# avionicsboard.net
KiCad netlist of a schematic drawn in EAGLE
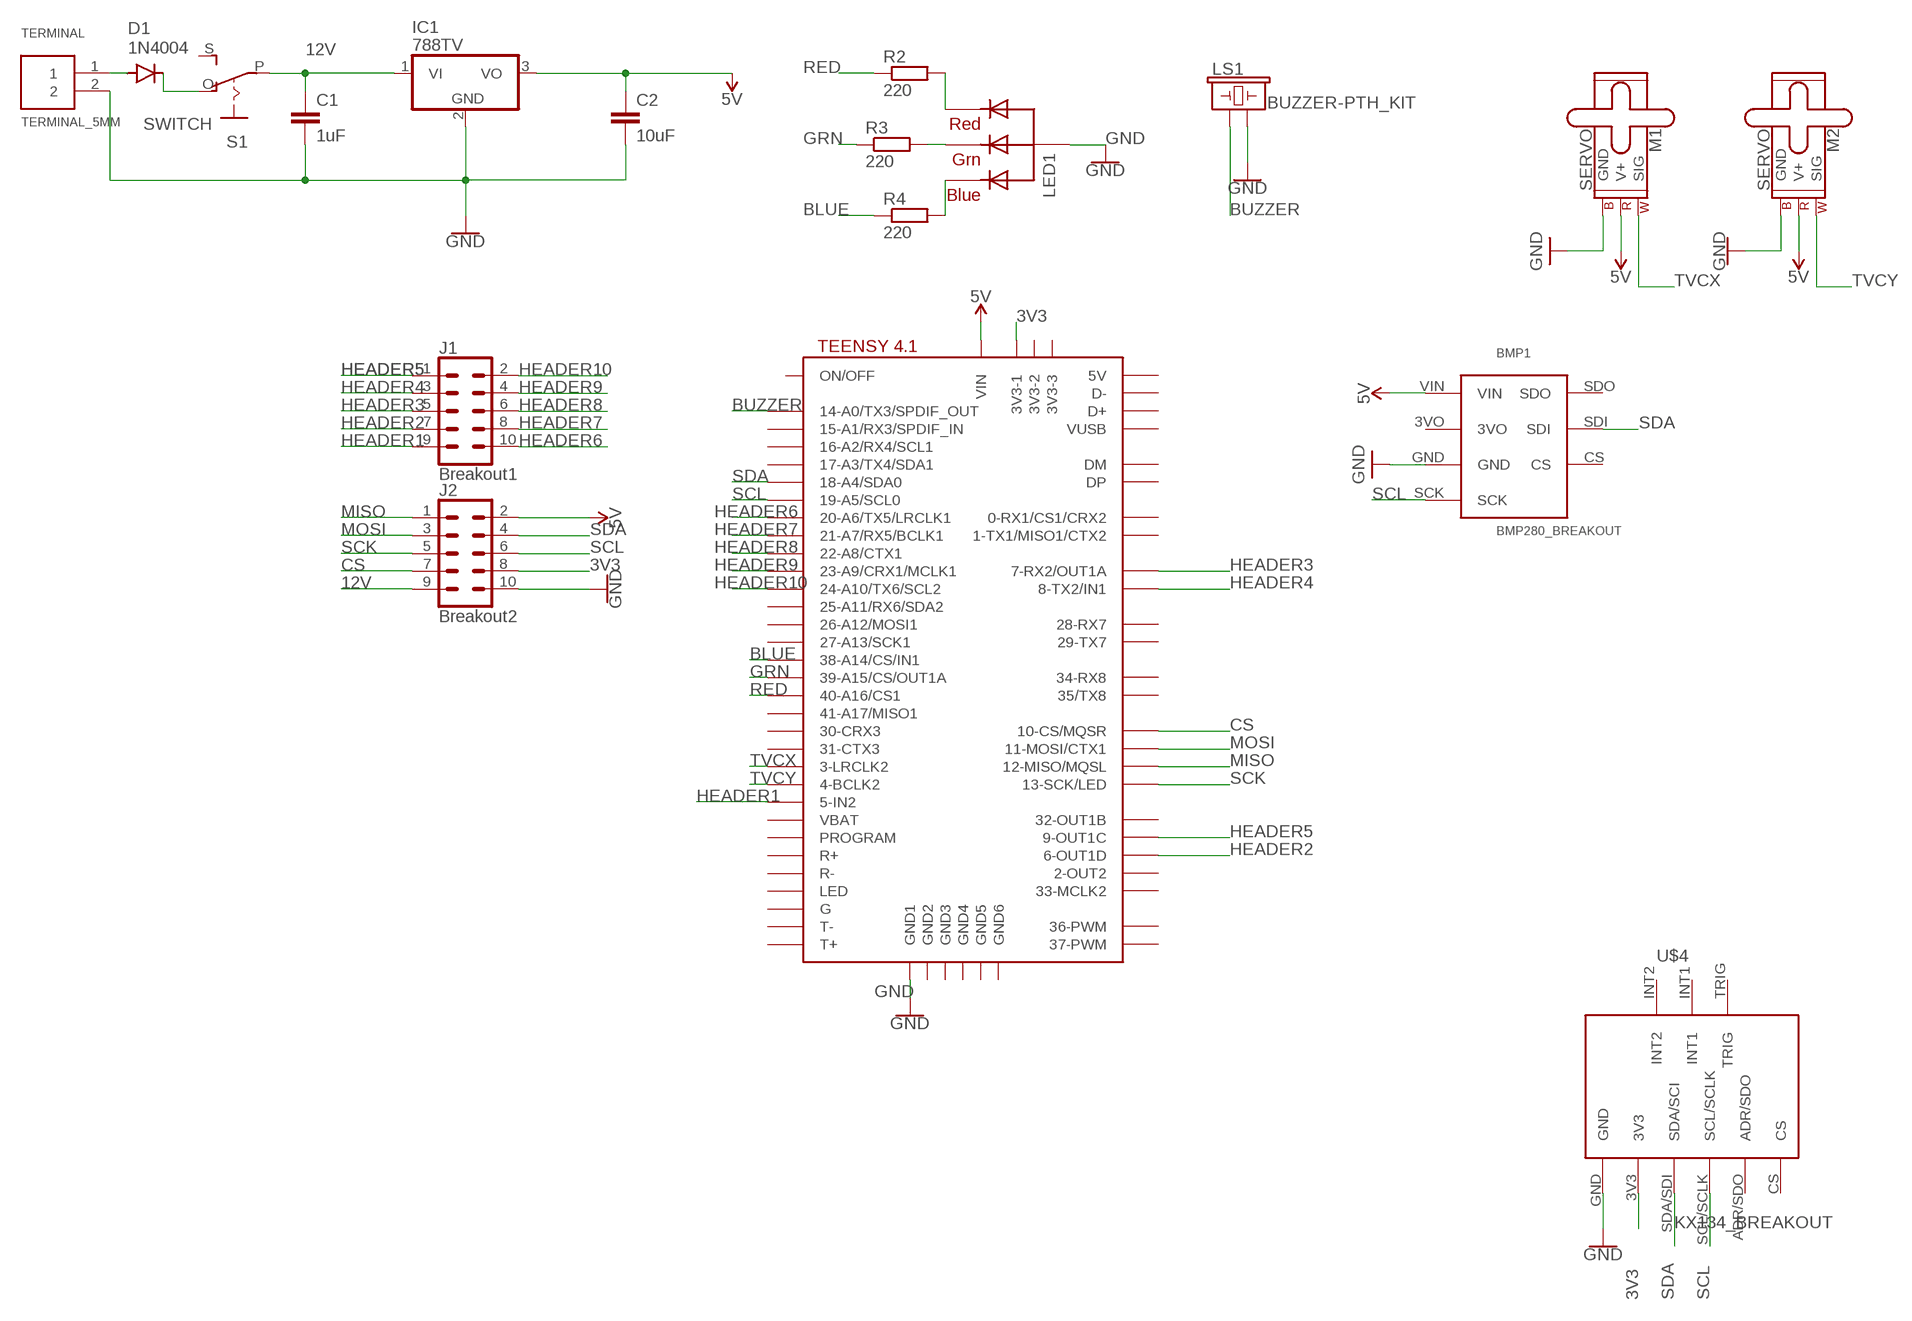
[diagram p0: schematic, sheet 1]

(export (version "E")
  (design (tool "Eeschema 10.0.6"))
  (components
    (comp (ref "BMP1")
      (value "BMP280_BREAKOUT")
      (footprint "eagle-import:BMP280_BREAKOUT")
      (libsource (lib "eagle-import") (part "BMP280_BREAKOUT"))
    )
    (comp (ref "C1")
      (value "1uF")
      (footprint "eagle-import:CAP-PTH-2.54")
      (libsource (lib "eagle-import") (part "22PF-PTH-2.54MM-200V-5%"))
    )
    (comp (ref "C2")
      (value "10uF")
      (footprint "eagle-import:CAP-PTH-2.54")
      (libsource (lib "eagle-import") (part "22PF-PTH-2.54MM-200V-5%"))
    )
    (comp (ref "D1")
      (value "1N4004")
      (footprint "eagle-import:DO41-10")
      (libsource (lib "eagle-import") (part "1N4004"))
    )
    (comp (ref "IC1")
      (value "788TV")
      (footprint "eagle-import:TO220V")
      (libsource (lib "eagle-import") (part "78TV8"))
    )
    (comp (ref "J1")
      (value "Breakout1")
      (footprint "eagle-import:2X5_NOSILK")
      (libsource (lib "eagle-import") (part "CONN_05X2NO_SILK"))
    )
    (comp (ref "J2")
      (value "Breakout2")
      (footprint "eagle-import:2X5_NOSILK")
      (libsource (lib "eagle-import") (part "CONN_05X2NO_SILK"))
    )
    (comp (ref "LED1")
      (value "RGBLED_CA-5MM")
      (footprint "eagle-import:LED5MMRGB")
      (libsource (lib "eagle-import") (part "RGBLED_CA-5MM"))
    )
    (comp (ref "LS1")
      (value "BUZZER-PTH_KIT")
      (footprint "eagle-import:BUZZER-12MM-KIT")
      (libsource (lib "eagle-import") (part "BUZZER-PTH_KIT"))
    )
    (comp (ref "M1")
      (value "SERVO")
      (footprint "eagle-import:1X03")
      (libsource (lib "eagle-import") (part "SERVO"))
    )
    (comp (ref "M2")
      (value "SERVO")
      (footprint "eagle-import:1X03")
      (libsource (lib "eagle-import") (part "SERVO"))
    )
    (comp (ref "R2")
      (value "220")
      (footprint "eagle-import:0204_7")
      (libsource (lib "eagle-import") (part "R-EU_0204/7"))
    )
    (comp (ref "R3")
      (value "220")
      (footprint "eagle-import:0204_7")
      (libsource (lib "eagle-import") (part "R-EU_0204/7"))
    )
    (comp (ref "R4")
      (value "220")
      (footprint "eagle-import:0204_7")
      (libsource (lib "eagle-import") (part "R-EU_0204/7"))
    )
    (comp (ref "S1")
      (value "SWITCH")
      (footprint "eagle-import:EG1218")
      (libsource (lib "eagle-import") (part "EG1218S"))
    )
    (comp (ref "TERMINAL")
      (value "TERMINAL_5MM")
      (footprint "eagle-import:TERMINAL_5MM")
      (libsource (lib "eagle-import") (part "TERMINAL_5MM"))
    )
    (comp (ref "U$1")
      (value "TEENSY41")
      (footprint "eagle-import:TEENSY41")
      (libsource (lib "eagle-import") (part "TEENSY41"))
    )
    (comp (ref "U$4")
      (value "KX134_BREAKOUT")
      (footprint "eagle-import:KX134_BREAKOUT")
      (libsource (lib "eagle-import") (part "KX134_BREAKOUT"))
    )
  )
  (nets
    (net (code "1") (name "/3V3") (class "Default")
      (node (ref "J2") (pin "8") (pinfunction "8_8") (pintype "passive"))
      (node (ref "U$1") (pin "3V3-1") (pinfunction "3V3-1_3V3-1") (pintype "bidirectional"))
      (node (ref "U$4") (pin "3V3") (pinfunction "3V3_3V3") (pintype "bidirectional"))
    )
    (net (code "2") (name "/12V") (class "Default")
      (node (ref "C1") (pin "1") (pinfunction "1_1") (pintype "passive"))
      (node (ref "IC1") (pin "1") (pinfunction "VI_1") (pintype "input"))
      (node (ref "J2") (pin "9") (pinfunction "9_9") (pintype "passive"))
      (node (ref "S1") (pin "P") (pinfunction "P_P") (pintype "passive"))
    )
    (net (code "3") (name "/BLUE") (class "Default")
      (node (ref "R4") (pin "1") (pinfunction "1_1") (pintype "passive"))
      (node (ref "U$1") (pin "38-A14/CS/IN1") (pinfunction "38-A14/CS/IN1_38-A14/CS/IN1") (pintype "bidirectional"))
    )
    (net (code "4") (name "/BUZZER") (class "Default")
      (node (ref "LS1") (pin "+") (pinfunction "1_+") (pintype "passive"))
      (node (ref "U$1") (pin "14-A0/TX3/SPDIF_OUT") (pinfunction "14-A0/TX3/SPDIF_OUT_14-A0/TX3/SPDIF_OUT") (pintype "bidirectional"))
    )
    (net (code "5") (name "/CS") (class "Default")
      (node (ref "J2") (pin "7") (pinfunction "7_7") (pintype "passive"))
      (node (ref "U$1") (pin "10-CS\\MQSR") (pinfunction "10-CS/MQSR_10-CS\\MQSR") (pintype "bidirectional"))
    )
    (net (code "6") (name "/GRN") (class "Default")
      (node (ref "R3") (pin "1") (pinfunction "1_1") (pintype "passive"))
      (node (ref "U$1") (pin "39-A15/CS/OUT1A") (pinfunction "39-A15/CS/OUT1A_39-A15/CS/OUT1A") (pintype "bidirectional"))
    )
    (net (code "7") (name "/HEADER1") (class "Default")
      (node (ref "J1") (pin "9") (pinfunction "9_9") (pintype "passive"))
      (node (ref "U$1") (pin "5-IN2") (pinfunction "5-IN2_5-IN2") (pintype "bidirectional"))
    )
    (net (code "8") (name "/HEADER2") (class "Default")
      (node (ref "J1") (pin "7") (pinfunction "7_7") (pintype "passive"))
      (node (ref "U$1") (pin "6-OUT1D") (pinfunction "6-OUT1D_6-OUT1D") (pintype "bidirectional"))
    )
    (net (code "9") (name "/HEADER3") (class "Default")
      (node (ref "J1") (pin "5") (pinfunction "5_5") (pintype "passive"))
      (node (ref "U$1") (pin "7-RX2/OUT1A") (pinfunction "7-RX2/OUT1A_7-RX2/OUT1A") (pintype "bidirectional"))
    )
    (net (code "10") (name "/HEADER4") (class "Default")
      (node (ref "J1") (pin "3") (pinfunction "3_3") (pintype "passive"))
      (node (ref "U$1") (pin "8-TX2/IN2") (pinfunction "8-TX2/IN1_8-TX2/IN2") (pintype "bidirectional"))
    )
    (net (code "11") (name "/HEADER5") (class "Default")
      (node (ref "J1") (pin "1") (pinfunction "1_1") (pintype "passive"))
      (node (ref "U$1") (pin "9-OUT1C") (pinfunction "9-OUT1C_9-OUT1C") (pintype "bidirectional"))
    )
    (net (code "12") (name "/HEADER6") (class "Default")
      (node (ref "J1") (pin "10") (pinfunction "10_10") (pintype "passive"))
      (node (ref "U$1") (pin "20-A6/TX5/LRCLK1") (pinfunction "20-A6/TX5/LRCLK1_20-A6/TX5/LRCLK1") (pintype "bidirectional"))
    )
    (net (code "13") (name "/HEADER7") (class "Default")
      (node (ref "J1") (pin "8") (pinfunction "8_8") (pintype "passive"))
      (node (ref "U$1") (pin "21-A7/RX5/BCLK1") (pinfunction "21-A7/RX5/BCLK1_21-A7/RX5/BCLK1") (pintype "bidirectional"))
    )
    (net (code "14") (name "/HEADER8") (class "Default")
      (node (ref "J1") (pin "6") (pinfunction "6_6") (pintype "passive"))
      (node (ref "U$1") (pin "22-A8/CTX1") (pinfunction "22-A8/CTX1_22-A8/CTX1") (pintype "bidirectional"))
    )
    (net (code "15") (name "/HEADER9") (class "Default")
      (node (ref "J1") (pin "4") (pinfunction "4_4") (pintype "passive"))
      (node (ref "U$1") (pin "23-A9/CRX1/MCLK1") (pinfunction "23-A9/CRX1/MCLK1_23-A9/CRX1/MCLK1") (pintype "bidirectional"))
    )
    (net (code "16") (name "/HEADER10") (class "Default")
      (node (ref "J1") (pin "2") (pinfunction "2_2") (pintype "passive"))
      (node (ref "U$1") (pin "24-A10/TX6/SCL2") (pinfunction "24-A10/TX6/SCL2_24-A10/TX6/SCL2") (pintype "bidirectional"))
    )
    (net (code "17") (name "/MISO") (class "Default")
      (node (ref "J2") (pin "1") (pinfunction "1_1") (pintype "passive"))
      (node (ref "U$1") (pin "12-MISO/MQSL") (pinfunction "12-MISO/MQSL_12-MISO/MQSL") (pintype "bidirectional"))
    )
    (net (code "18") (name "/MOSI") (class "Default")
      (node (ref "J2") (pin "3") (pinfunction "3_3") (pintype "passive"))
      (node (ref "U$1") (pin "11-MOSI/CTX1") (pinfunction "11-MOSI/CTX1_11-MOSI/CTX1") (pintype "bidirectional"))
    )
    (net (code "19") (name "/RED") (class "Default")
      (node (ref "R2") (pin "1") (pinfunction "1_1") (pintype "passive"))
      (node (ref "U$1") (pin "40-A16/CS1") (pinfunction "40-A16/CS1_40-A16/CS1") (pintype "bidirectional"))
    )
    (net (code "20") (name "/SCK") (class "Default")
      (node (ref "J2") (pin "5") (pinfunction "5_5") (pintype "passive"))
      (node (ref "U$1") (pin "13-SCK/LED") (pinfunction "13-SCK/LED_13-SCK/LED") (pintype "bidirectional"))
    )
    (net (code "21") (name "/SCL") (class "Default")
      (node (ref "BMP1") (pin "SCK") (pinfunction "SCK_SCK") (pintype "bidirectional"))
      (node (ref "J2") (pin "6") (pinfunction "6_6") (pintype "passive"))
      (node (ref "U$1") (pin "19-A5/SCL0") (pinfunction "19-A5/SCL0_19-A5/SCL0") (pintype "bidirectional"))
      (node (ref "U$4") (pin "SCL/SCLK") (pinfunction "SCL/SCLK_SCL/SCLK") (pintype "bidirectional"))
    )
    (net (code "22") (name "/SDA") (class "Default")
      (node (ref "BMP1") (pin "SDI") (pinfunction "SDI_SDI") (pintype "bidirectional"))
      (node (ref "J2") (pin "4") (pinfunction "4_4") (pintype "passive"))
      (node (ref "U$1") (pin "18-A4/SDA0") (pinfunction "18-A4/SDA0_18-A4/SDA0") (pintype "bidirectional"))
      (node (ref "U$4") (pin "SDA/SDI") (pinfunction "SDA/SCI_SDA/SDI") (pintype "bidirectional"))
    )
    (net (code "23") (name "/TVCX") (class "Default")
      (node (ref "M1") (pin "1") (pinfunction "SIG_1") (pintype "bidirectional"))
      (node (ref "U$1") (pin "3-LRCLK2") (pinfunction "3-LRCLK2_3-LRCLK2") (pintype "bidirectional"))
    )
    (net (code "24") (name "/TVCY") (class "Default")
      (node (ref "M2") (pin "1") (pinfunction "SIG_1") (pintype "bidirectional"))
      (node (ref "U$1") (pin "4-BCLK2") (pinfunction "4-BCLK2_4-BCLK2") (pintype "bidirectional"))
    )
    (net (code "25") (name "5V") (class "Default")
      (node (ref "BMP1") (pin "VIN") (pinfunction "VIN_VIN") (pintype "bidirectional"))
      (node (ref "C2") (pin "1") (pinfunction "1_1") (pintype "passive"))
      (node (ref "IC1") (pin "3") (pinfunction "VO_3") (pintype "passive"))
      (node (ref "J2") (pin "2") (pinfunction "2_2") (pintype "passive"))
      (node (ref "M1") (pin "2") (pinfunction "V+_2") (pintype "bidirectional"))
      (node (ref "M2") (pin "2") (pinfunction "V+_2") (pintype "bidirectional"))
      (node (ref "U$1") (pin "VIN") (pinfunction "VIN_VIN") (pintype "bidirectional"))
    )
    (net (code "26") (name "GND") (class "Default")
      (node (ref "BMP1") (pin "GND") (pinfunction "GND_GND") (pintype "bidirectional"))
      (node (ref "C1") (pin "2") (pinfunction "2_2") (pintype "passive"))
      (node (ref "C2") (pin "2") (pinfunction "2_2") (pintype "passive"))
      (node (ref "IC1") (pin "2") (pinfunction "GND_2") (pintype "passive"))
      (node (ref "J2") (pin "10") (pinfunction "10_10") (pintype "passive"))
      (node (ref "LED1") (pin "2") (pinfunction "VCC_2") (pintype "bidirectional"))
      (node (ref "LS1") (pin "-") (pinfunction "2_-") (pintype "passive"))
      (node (ref "M1") (pin "3") (pinfunction "GND_3") (pintype "bidirectional"))
      (node (ref "M2") (pin "3") (pinfunction "GND_3") (pintype "bidirectional"))
      (node (ref "TERMINAL") (pin "2") (pinfunction "2_2") (pintype "bidirectional"))
      (node (ref "U$1") (pin "GND1") (pinfunction "GND1_GND1") (pintype "bidirectional"))
      (node (ref "U$4") (pin "GND") (pinfunction "GND_GND") (pintype "bidirectional"))
    )
    (net (code "27") (name "Net-(D1-PadA)") (class "Default")
      (node (ref "D1") (pin "A") (pinfunction "A_A") (pintype "passive"))
      (node (ref "TERMINAL") (pin "1") (pinfunction "1_1") (pintype "bidirectional"))
    )
    (net (code "28") (name "Net-(D1-PadC)") (class "Default")
      (node (ref "D1") (pin "C") (pinfunction "C_C") (pintype "passive"))
      (node (ref "S1") (pin "O") (pinfunction "O_O") (pintype "passive"))
    )
    (net (code "29") (name "Net-(LED1-BLUE)") (class "Default")
      (node (ref "LED1") (pin "4") (pinfunction "BLUE_4") (pintype "bidirectional"))
      (node (ref "R4") (pin "2") (pinfunction "2_2") (pintype "passive"))
    )
    (net (code "30") (name "Net-(LED1-GREEN)") (class "Default")
      (node (ref "LED1") (pin "3") (pinfunction "GREEN_3") (pintype "bidirectional"))
      (node (ref "R3") (pin "2") (pinfunction "2_2") (pintype "passive"))
    )
    (net (code "31") (name "Net-(LED1-RED)") (class "Default")
      (node (ref "LED1") (pin "1") (pinfunction "RED_1") (pintype "bidirectional"))
      (node (ref "R2") (pin "2") (pinfunction "2_2") (pintype "passive"))
    )
    (net (code "32") (name "unconnected-(BMP1-Pad3VO)") (class "Default")
      (node (ref "BMP1") (pin "3VO") (pinfunction "3VO_3VO") (pintype "bidirectional"))
    )
    (net (code "33") (name "unconnected-(BMP1-PadCS)") (class "Default")
      (node (ref "BMP1") (pin "CS") (pinfunction "CS_CS") (pintype "bidirectional"))
    )
    (net (code "34") (name "unconnected-(BMP1-PadSDO)") (class "Default")
      (node (ref "BMP1") (pin "SDO") (pinfunction "SDO_SDO") (pintype "bidirectional"))
    )
    (net (code "35") (name "unconnected-(S1-PadS)") (class "Default")
      (node (ref "S1") (pin "S") (pinfunction "S_S") (pintype "passive"))
    )
    (net (code "36") (name "unconnected-(U$1-5V-Pad+5V)") (class "Default")
      (node (ref "U$1") (pin "+5V") (pinfunction "5V_+5V") (pintype "bidirectional"))
    )
    (net (code "37") (name "unconnected-(U$1-35{slash}TX8-Pad35-TX8)") (class "Default")
      (node (ref "U$1") (pin "35-TX8") (pinfunction "35/TX8_35-TX8") (pintype "bidirectional"))
    )
    (net (code "38") (name "unconnected-(U$1-Pad0-RX1{slash}CS1{slash}CRX2)") (class "Default")
      (node (ref "U$1") (pin "0-RX1/CS1/CRX2") (pinfunction "0-RX1/CS1/CRX2_0-RX1/CS1/CRX2") (pintype "bidirectional"))
    )
    (net (code "39") (name "unconnected-(U$1-Pad1-TX1{slash}MISO1{slash}CTX2)") (class "Default")
      (node (ref "U$1") (pin "1-TX1/MISO1/CTX2") (pinfunction "1-TX1/MISO1/CTX2_1-TX1/MISO1/CTX2") (pintype "bidirectional"))
    )
    (net (code "40") (name "unconnected-(U$1-Pad2-OUT2)") (class "Default")
      (node (ref "U$1") (pin "2-OUT2") (pinfunction "2-OUT2_2-OUT2") (pintype "bidirectional"))
    )
    (net (code "41") (name "unconnected-(U$1-Pad3V3-2)") (class "Default")
      (node (ref "U$1") (pin "3V3-2") (pinfunction "3V3-2_3V3-2") (pintype "bidirectional"))
    )
    (net (code "42") (name "unconnected-(U$1-Pad3V3-3)") (class "Default")
      (node (ref "U$1") (pin "3V3-3") (pinfunction "3V3-3_3V3-3") (pintype "bidirectional"))
    )
    (net (code "43") (name "unconnected-(U$1-Pad15-A1{slash}RX3{slash}SPDIF_IN)") (class "Default")
      (node (ref "U$1") (pin "15-A1/RX3/SPDIF_IN") (pinfunction "15-A1/RX3/SPDIF_IN_15-A1/RX3/SPDIF_IN") (pintype "bidirectional"))
    )
    (net (code "44") (name "unconnected-(U$1-Pad16-A2{slash}RX4{slash}SCL1)") (class "Default")
      (node (ref "U$1") (pin "16-A2/RX4/SCL1") (pinfunction "16-A2/RX4/SCL1_16-A2/RX4/SCL1") (pintype "bidirectional"))
    )
    (net (code "45") (name "unconnected-(U$1-Pad17-A3{slash}TX4{slash}SDA1)") (class "Default")
      (node (ref "U$1") (pin "17-A3/TX4/SDA1") (pinfunction "17-A3/TX4/SDA1_17-A3/TX4/SDA1") (pintype "bidirectional"))
    )
    (net (code "46") (name "unconnected-(U$1-Pad25-A11{slash}RX6{slash}SDA2)") (class "Default")
      (node (ref "U$1") (pin "25-A11/RX6/SDA2") (pinfunction "25-A11/RX6/SDA2_25-A11/RX6/SDA2") (pintype "bidirectional"))
    )
    (net (code "47") (name "unconnected-(U$1-Pad26-A12{slash}MOSI1)") (class "Default")
      (node (ref "U$1") (pin "26-A12/MOSI1") (pinfunction "26-A12/MOSI1_26-A12/MOSI1") (pintype "bidirectional"))
    )
    (net (code "48") (name "unconnected-(U$1-Pad27-A13{slash}SCK1)") (class "Default")
      (node (ref "U$1") (pin "27-A13/SCK1") (pinfunction "27-A13/SCK1_27-A13/SCK1") (pintype "bidirectional"))
    )
    (net (code "49") (name "unconnected-(U$1-Pad28-RX7)") (class "Default")
      (node (ref "U$1") (pin "28-RX7") (pinfunction "28-RX7_28-RX7") (pintype "bidirectional"))
    )
    (net (code "50") (name "unconnected-(U$1-Pad29-TX7)") (class "Default")
      (node (ref "U$1") (pin "29-TX7") (pinfunction "29-TX7_29-TX7") (pintype "bidirectional"))
    )
    (net (code "51") (name "unconnected-(U$1-Pad30-CRX3)") (class "Default")
      (node (ref "U$1") (pin "30-CRX3") (pinfunction "30-CRX3_30-CRX3") (pintype "bidirectional"))
    )
    (net (code "52") (name "unconnected-(U$1-Pad31-CTX3)") (class "Default")
      (node (ref "U$1") (pin "31-CTX3") (pinfunction "31-CTX3_31-CTX3") (pintype "bidirectional"))
    )
    (net (code "53") (name "unconnected-(U$1-Pad32-OUT1B)") (class "Default")
      (node (ref "U$1") (pin "32-OUT1B") (pinfunction "32-OUT1B_32-OUT1B") (pintype "bidirectional"))
    )
    (net (code "54") (name "unconnected-(U$1-Pad33-MCLK2)") (class "Default")
      (node (ref "U$1") (pin "33-MCLK2") (pinfunction "33-MCLK2_33-MCLK2") (pintype "bidirectional"))
    )
    (net (code "55") (name "unconnected-(U$1-Pad34-RX8)") (class "Default")
      (node (ref "U$1") (pin "34-RX8") (pinfunction "34-RX8_34-RX8") (pintype "bidirectional"))
    )
    (net (code "56") (name "unconnected-(U$1-Pad36-PWM)") (class "Default")
      (node (ref "U$1") (pin "36-PWM") (pinfunction "36-PWM_36-PWM") (pintype "bidirectional"))
    )
    (net (code "57") (name "unconnected-(U$1-Pad37-PWM)") (class "Default")
      (node (ref "U$1") (pin "37-PWM") (pinfunction "37-PWM_37-PWM") (pintype "bidirectional"))
    )
    (net (code "58") (name "unconnected-(U$1-Pad41-A17{slash}MISO1)") (class "Default")
      (node (ref "U$1") (pin "41-A17/MISO1") (pinfunction "41-A17/MISO1_41-A17/MISO1") (pintype "bidirectional"))
    )
    (net (code "59") (name "unconnected-(U$1-PadD+)") (class "Default")
      (node (ref "U$1") (pin "D+") (pinfunction "D+_D+") (pintype "bidirectional"))
    )
    (net (code "60") (name "unconnected-(U$1-PadD-)") (class "Default")
      (node (ref "U$1") (pin "D-") (pinfunction "D-_D-") (pintype "bidirectional"))
    )
    (net (code "61") (name "unconnected-(U$1-PadDM)") (class "Default")
      (node (ref "U$1") (pin "DM") (pinfunction "DM_DM") (pintype "bidirectional"))
    )
    (net (code "62") (name "unconnected-(U$1-PadDP)") (class "Default")
      (node (ref "U$1") (pin "DP") (pinfunction "DP_DP") (pintype "bidirectional"))
    )
    (net (code "63") (name "unconnected-(U$1-PadG)") (class "Default")
      (node (ref "U$1") (pin "G") (pinfunction "G_G") (pintype "bidirectional"))
    )
    (net (code "64") (name "unconnected-(U$1-PadGND2)") (class "Default")
      (node (ref "U$1") (pin "GND2") (pinfunction "GND2_GND2") (pintype "bidirectional"))
    )
    (net (code "65") (name "unconnected-(U$1-PadGND3)") (class "Default")
      (node (ref "U$1") (pin "GND3") (pinfunction "GND3_GND3") (pintype "bidirectional"))
    )
    (net (code "66") (name "unconnected-(U$1-PadGND4)") (class "Default")
      (node (ref "U$1") (pin "GND4") (pinfunction "GND4_GND4") (pintype "bidirectional"))
    )
    (net (code "67") (name "unconnected-(U$1-PadGND5)") (class "Default")
      (node (ref "U$1") (pin "GND5") (pinfunction "GND5_GND5") (pintype "bidirectional"))
    )
    (net (code "68") (name "unconnected-(U$1-PadGND6)") (class "Default")
      (node (ref "U$1") (pin "GND6") (pinfunction "GND6_GND6") (pintype "bidirectional"))
    )
    (net (code "69") (name "unconnected-(U$1-PadLED)") (class "Default")
      (node (ref "U$1") (pin "LED") (pinfunction "LED_LED") (pintype "bidirectional"))
    )
    (net (code "70") (name "unconnected-(U$1-PadON{slash}OFF)") (class "Default")
      (node (ref "U$1") (pin "ON/OFF") (pinfunction "ON/OFF_ON/OFF") (pintype "bidirectional"))
    )
    (net (code "71") (name "unconnected-(U$1-PadPROGRAM)") (class "Default")
      (node (ref "U$1") (pin "PROGRAM") (pinfunction "PROGRAM_PROGRAM") (pintype "bidirectional"))
    )
    (net (code "72") (name "unconnected-(U$1-PadR+)") (class "Default")
      (node (ref "U$1") (pin "R+") (pinfunction "R+_R+") (pintype "bidirectional"))
    )
    (net (code "73") (name "unconnected-(U$1-PadR-)") (class "Default")
      (node (ref "U$1") (pin "R-") (pinfunction "R-_R-") (pintype "bidirectional"))
    )
    (net (code "74") (name "unconnected-(U$1-PadT+)") (class "Default")
      (node (ref "U$1") (pin "T+") (pinfunction "T+_T+") (pintype "bidirectional"))
    )
    (net (code "75") (name "unconnected-(U$1-PadT-)") (class "Default")
      (node (ref "U$1") (pin "T-") (pinfunction "T-_T-") (pintype "bidirectional"))
    )
    (net (code "76") (name "unconnected-(U$1-PadVBAT)") (class "Default")
      (node (ref "U$1") (pin "VBAT") (pinfunction "VBAT_VBAT") (pintype "bidirectional"))
    )
    (net (code "77") (name "unconnected-(U$1-PadVUSB)") (class "Default")
      (node (ref "U$1") (pin "VUSB") (pinfunction "VUSB_VUSB") (pintype "bidirectional"))
    )
    (net (code "78") (name "unconnected-(U$4-PadADR{slash}SDO)") (class "Default")
      (node (ref "U$4") (pin "ADR/SDO") (pinfunction "ADR/SDO_ADR/SDO") (pintype "bidirectional"))
    )
    (net (code "79") (name "unconnected-(U$4-PadCS)") (class "Default")
      (node (ref "U$4") (pin "CS") (pinfunction "CS_CS") (pintype "bidirectional"))
    )
    (net (code "80") (name "unconnected-(U$4-PadINT1)") (class "Default")
      (node (ref "U$4") (pin "INT1") (pinfunction "INT1_INT1") (pintype "bidirectional"))
    )
    (net (code "81") (name "unconnected-(U$4-PadINT2)") (class "Default")
      (node (ref "U$4") (pin "INT2") (pinfunction "INT2_INT2") (pintype "bidirectional"))
    )
    (net (code "82") (name "unconnected-(U$4-PadTRIG)") (class "Default")
      (node (ref "U$4") (pin "TRIG") (pinfunction "TRIG_TRIG") (pintype "bidirectional"))
    )
  )
)
